# MCU.net
KiCad netlist of a schematic drawn in Altium Designer
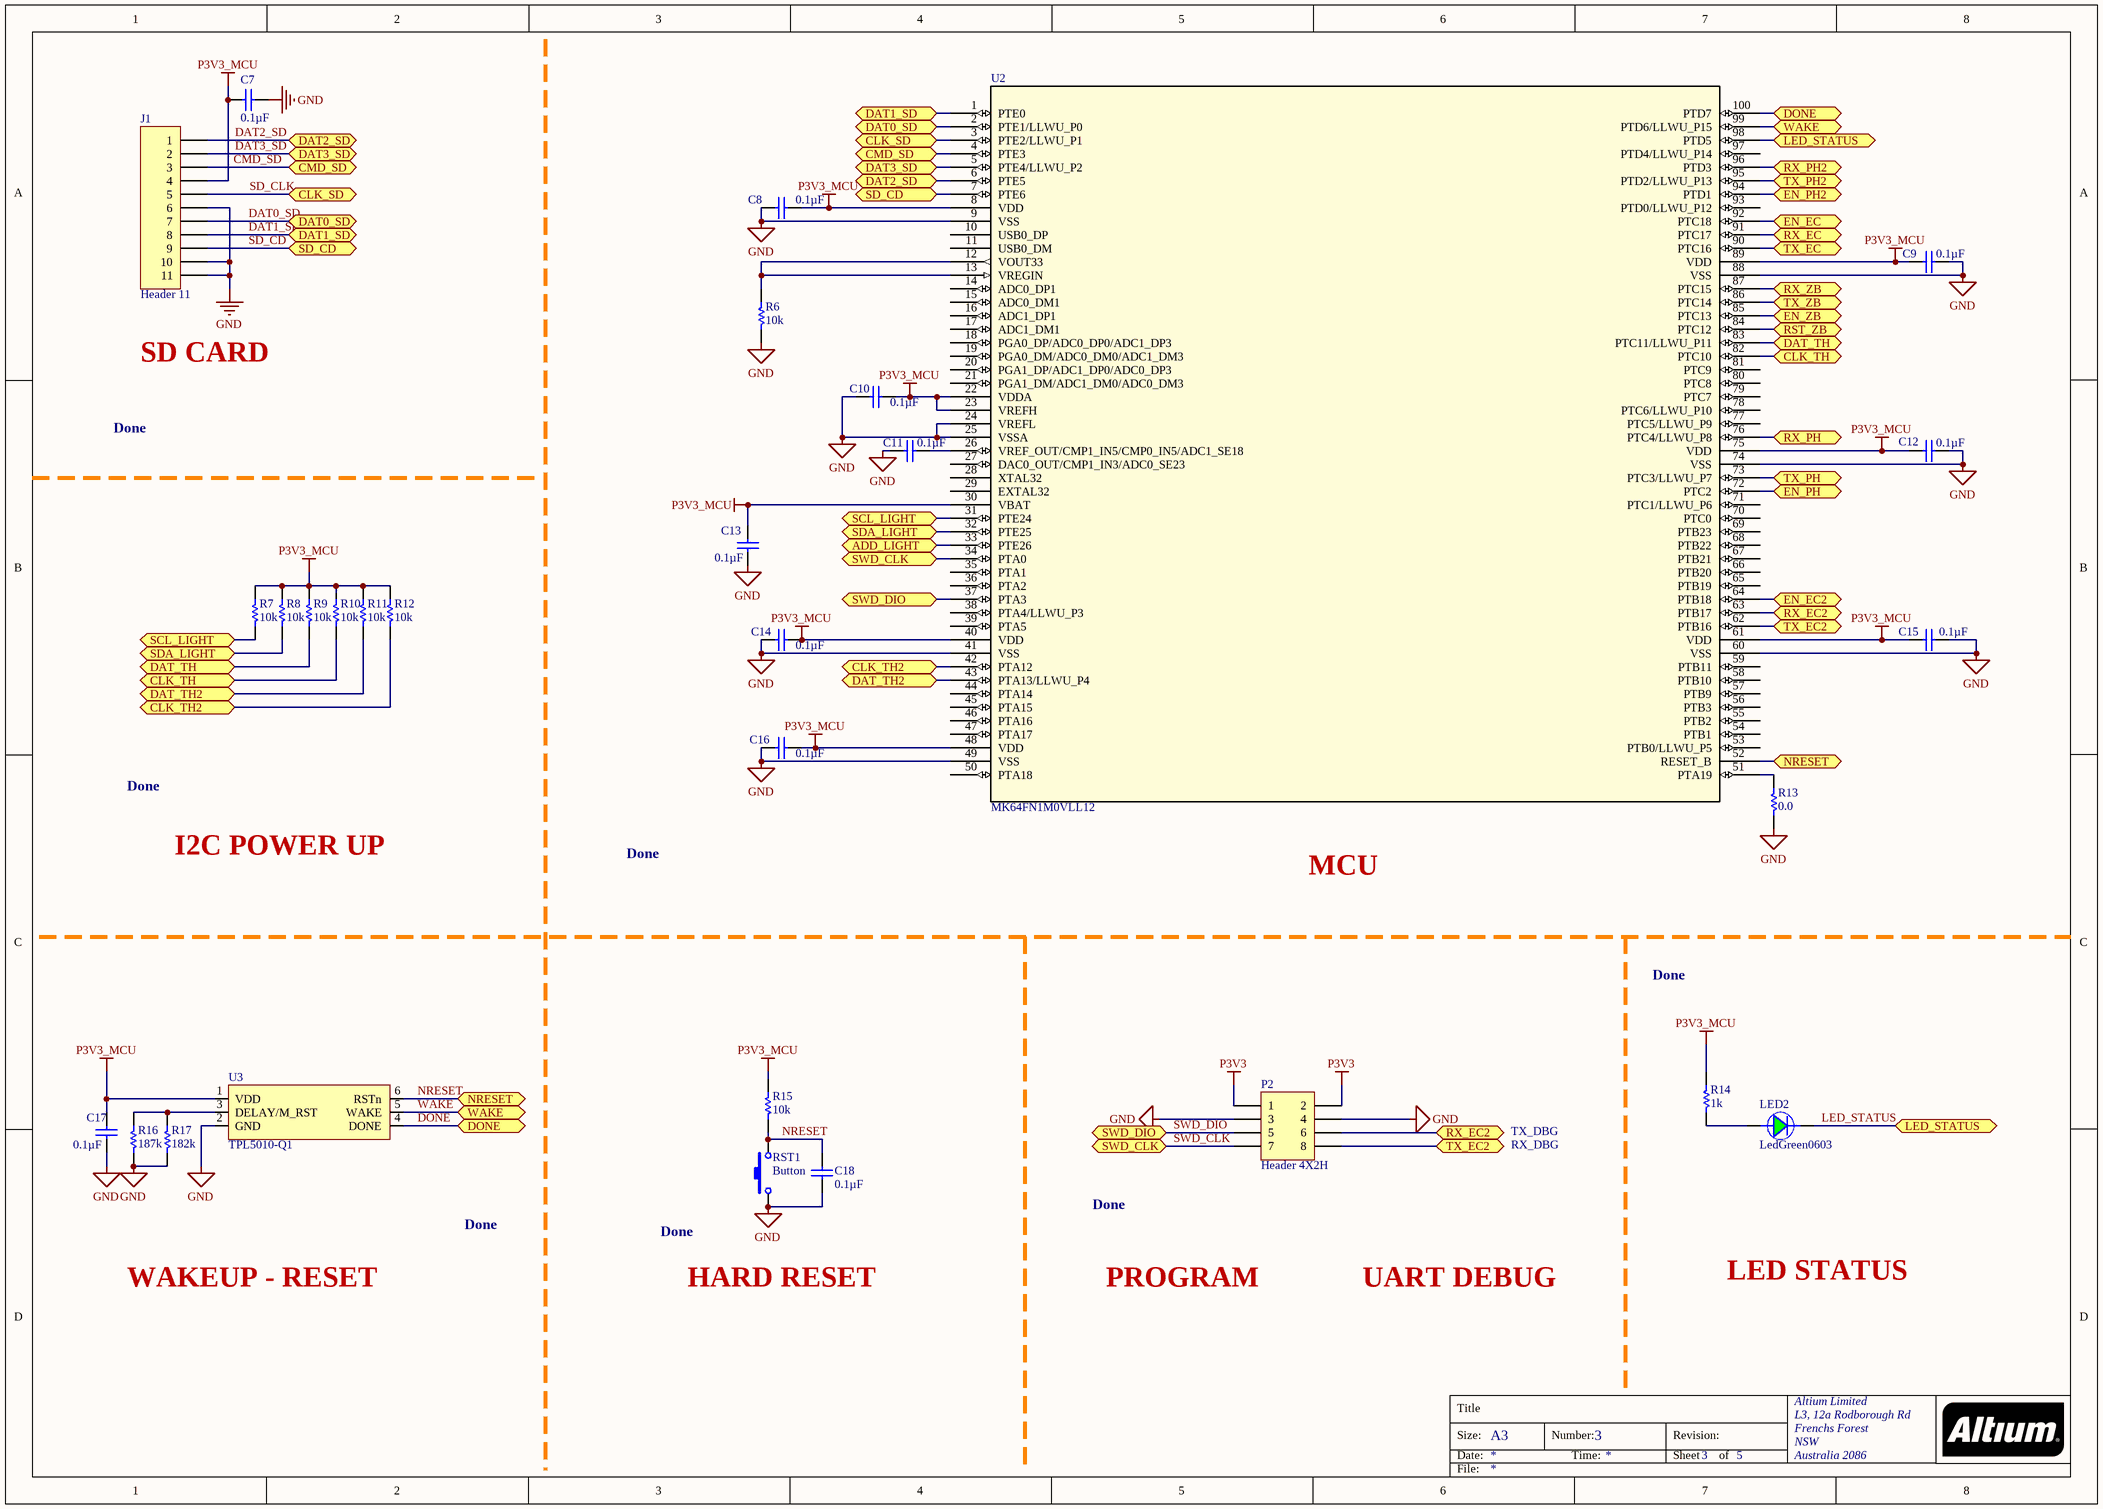
[diagram p0: MCU.SchDoc]

(export (version "E")
  (design (tool "Eeschema 10.0.6"))
  (components
    (comp (ref "C7")
      (value "0.1µF")
      (footprint "C0402M")
      (description "CAP CER 0.1UF 10V X7R 0402")
      (fields
        (field (name "MANUFACTURER") "Taiyo Yuden")
        (field (name "MANUFACTURER PART NUMBER") "LMK105B7104KVHF")
      )
      (libsource (lib "BinhLib") (part "CAP0.1u0402"))
    )
    (comp (ref "C8")
      (value "0.1µF")
      (footprint "C0402M")
      (description "CAP CER 0.1UF 10V X7R 0402")
      (fields
        (field (name "MANUFACTURER") "Taiyo Yuden")
        (field (name "MANUFACTURER PART NUMBER") "LMK105B7104KVHF")
      )
      (libsource (lib "BinhLib") (part "CAP0.1u0402"))
    )
    (comp (ref "C9")
      (value "0.1µF")
      (footprint "C0402M")
      (description "CAP CER 0.1UF 10V X7R 0402")
      (fields
        (field (name "MANUFACTURER") "Taiyo Yuden")
        (field (name "MANUFACTURER PART NUMBER") "LMK105B7104KVHF")
      )
      (libsource (lib "BinhLib") (part "CAP0.1u0402"))
    )
    (comp (ref "C10")
      (value "0.1µF")
      (footprint "C0402M")
      (description "CAP CER 0.1UF 10V X7R 0402")
      (fields
        (field (name "MANUFACTURER") "Taiyo Yuden")
        (field (name "MANUFACTURER PART NUMBER") "LMK105B7104KVHF")
      )
      (libsource (lib "BinhLib") (part "CAP0.1u0402"))
    )
    (comp (ref "C11")
      (value "0.1µF")
      (footprint "C0402M")
      (description "CAP CER 0.1UF 10V X7R 0402")
      (fields
        (field (name "MANUFACTURER") "Taiyo Yuden")
        (field (name "MANUFACTURER PART NUMBER") "LMK105B7104KVHF")
      )
      (libsource (lib "BinhLib") (part "CAP0.1u0402"))
    )
    (comp (ref "C12")
      (value "0.1µF")
      (footprint "C0402M")
      (description "CAP CER 0.1UF 10V X7R 0402")
      (fields
        (field (name "MANUFACTURER") "Taiyo Yuden")
        (field (name "MANUFACTURER PART NUMBER") "LMK105B7104KVHF")
      )
      (libsource (lib "BinhLib") (part "CAP0.1u0402"))
    )
    (comp (ref "C13")
      (value "0.1µF")
      (footprint "C0402M")
      (description "CAP CER 0.1UF 10V X7R 0402")
      (fields
        (field (name "MANUFACTURER") "Taiyo Yuden")
        (field (name "MANUFACTURER PART NUMBER") "LMK105B7104KVHF")
      )
      (libsource (lib "BinhLib") (part "CAP0.1u0402"))
    )
    (comp (ref "C14")
      (value "0.1µF")
      (footprint "C0402M")
      (description "CAP CER 0.1UF 10V X7R 0402")
      (fields
        (field (name "MANUFACTURER") "Taiyo Yuden")
        (field (name "MANUFACTURER PART NUMBER") "LMK105B7104KVHF")
      )
      (libsource (lib "BinhLib") (part "CAP0.1u0402"))
    )
    (comp (ref "C15")
      (value "0.1µF")
      (footprint "C0402M")
      (description "CAP CER 0.1UF 10V X7R 0402")
      (fields
        (field (name "MANUFACTURER") "Taiyo Yuden")
        (field (name "MANUFACTURER PART NUMBER") "LMK105B7104KVHF")
      )
      (libsource (lib "BinhLib") (part "CAP0.1u0402"))
    )
    (comp (ref "C16")
      (value "0.1µF")
      (footprint "C0402M")
      (description "CAP CER 0.1UF 10V X7R 0402")
      (fields
        (field (name "MANUFACTURER") "Taiyo Yuden")
        (field (name "MANUFACTURER PART NUMBER") "LMK105B7104KVHF")
      )
      (libsource (lib "BinhLib") (part "CAP0.1u0402"))
    )
    (comp (ref "C17")
      (value "0.1µF")
      (footprint "C0402M")
      (description "CAP CER 0.1UF 10V X7R 0402")
      (fields
        (field (name "MANUFACTURER") "Taiyo Yuden")
        (field (name "MANUFACTURER PART NUMBER") "LMK105B7104KVHF")
      )
      (libsource (lib "BinhLib") (part "CAP0.1u0402"))
    )
    (comp (ref "C18")
      (value "0.1µF")
      (footprint "C0402M")
      (description "CAP CER 0.1UF 10V X7R 0402")
      (fields
        (field (name "MANUFACTURER") "Taiyo Yuden")
        (field (name "MANUFACTURER PART NUMBER") "LMK105B7104KVHF")
      )
      (libsource (lib "BinhLib") (part "CAP0.1u0402"))
    )
    (comp (ref "J1")
      (value "Header 11")
      (footprint "TF_V3")
      (description "Header, 11-Pin")
      (fields (field (name "PUBLISHER") "Altium Limited"))
      (libsource (lib "Miscellaneous Connectors") (part "Header 11"))
    )
    (comp (ref "LED2")
      (value "LedGreen0603")
      (footprint "0603LED-GREEN")
      (description "LED GREEN CLEAR 0603 SMD")
      (fields
        (field (name "MANUFACTURER") "Everlight Electronics Co Ltd")
        (field (name "MANUFACTURER PART NUMBER") "QTLP601C4TR")
      )
      (libsource (lib "BinhLib") (part "LedGreen0603"))
    )
    (comp (ref "P2")
      (value "Header 4X2H")
      (footprint "HDR2X4")
      (description "Header, 4-Pin, Dual row, Right Angle")
      (fields (field (name "PUBLISHER") "Altium Limited"))
      (libsource (lib "BinhLib") (part "Header 4X2H"))
    )
    (comp (ref "R6")
      (value "10k")
      (footprint "R0603M")
      (description "RES SMD 10K OHM 1% 1/10W 0603")
      (fields
        (field (name "MANUFACTURER") "Panasonic Electronic Components")
        (field (name "MANUFACTURER PART NUMBER") "ERJ-3EKF1002V")
      )
      (libsource (lib "BinhLib") (part "RES10k0603"))
    )
    (comp (ref "R7")
      (value "10k")
      (footprint "R0603M")
      (description "RES SMD 10K OHM 1% 1/10W 0603")
      (fields
        (field (name "MANUFACTURER") "Panasonic Electronic Components")
        (field (name "MANUFACTURER PART NUMBER") "ERJ-3EKF1002V")
      )
      (libsource (lib "BinhLib") (part "RES10k0603"))
    )
    (comp (ref "R8")
      (value "10k")
      (footprint "R0603M")
      (description "RES SMD 10K OHM 1% 1/10W 0603")
      (fields
        (field (name "MANUFACTURER") "Panasonic Electronic Components")
        (field (name "MANUFACTURER PART NUMBER") "ERJ-3EKF1002V")
      )
      (libsource (lib "BinhLib") (part "RES10k0603"))
    )
    (comp (ref "R9")
      (value "10k")
      (footprint "R0603M")
      (description "RES SMD 10K OHM 1% 1/10W 0603")
      (fields
        (field (name "MANUFACTURER") "Panasonic Electronic Components")
        (field (name "MANUFACTURER PART NUMBER") "ERJ-3EKF1002V")
      )
      (libsource (lib "BinhLib") (part "RES10k0603"))
    )
    (comp (ref "R10")
      (value "10k")
      (footprint "R0603M")
      (description "RES SMD 10K OHM 1% 1/10W 0603")
      (fields
        (field (name "MANUFACTURER") "Panasonic Electronic Components")
        (field (name "MANUFACTURER PART NUMBER") "ERJ-3EKF1002V")
      )
      (libsource (lib "BinhLib") (part "RES10k0603"))
    )
    (comp (ref "R11")
      (value "10k")
      (footprint "R0603M")
      (description "RES SMD 10K OHM 1% 1/10W 0603")
      (fields
        (field (name "MANUFACTURER") "Panasonic Electronic Components")
        (field (name "MANUFACTURER PART NUMBER") "ERJ-3EKF1002V")
      )
      (libsource (lib "BinhLib") (part "RES10k0603"))
    )
    (comp (ref "R12")
      (value "10k")
      (footprint "R0603M")
      (description "RES SMD 10K OHM 1% 1/10W 0603")
      (fields
        (field (name "MANUFACTURER") "Panasonic Electronic Components")
        (field (name "MANUFACTURER PART NUMBER") "ERJ-3EKF1002V")
      )
      (libsource (lib "BinhLib") (part "RES10k0603"))
    )
    (comp (ref "R13")
      (value "0.0")
      (footprint "R0603M")
      (description "RES SMD 0.0OHM JUMPER 1/10W 0603")
      (fields
        (field (name "MANUFACTURER") "Panasonic Electronic Components")
        (field (name "MANUFACTURER PART NUMBER") "ERJ-3GEY0R00V")
      )
      (libsource (lib "BinhLib") (part "RES00603"))
    )
    (comp (ref "R14")
      (value "1k")
      (footprint "R0603M")
      (description "RES SMD 1K OHM 1% 1/10W 0603")
      (fields
        (field (name "MANUFACTURER") "Panasonic Electronic Components")
        (field (name "MANUFACTURER PART NUMBER") "ERJ-3EKF1001V")
      )
      (libsource (lib "BinhLib") (part "RES1k0603"))
    )
    (comp (ref "R15")
      (value "10k")
      (footprint "R0603M")
      (description "RES SMD 10K OHM 1% 1/10W 0603")
      (fields
        (field (name "MANUFACTURER") "Panasonic Electronic Components")
        (field (name "MANUFACTURER PART NUMBER") "ERJ-3EKF1002V")
      )
      (libsource (lib "BinhLib") (part "RES10k0603"))
    )
    (comp (ref "R16")
      (value "187k")
      (footprint "R0603M")
      (description "RES SMD 187K OHM 1% 1/10W 0603")
      (fields
        (field (name "MANUFACTURER") "Panasonic Electronic Components")
        (field (name "MANUFACTURER PART NUMBER") "ERJ-3EKF1873V")
      )
      (libsource (lib "BinhLib") (part "Resistor"))
    )
    (comp (ref "R17")
      (value "182k")
      (footprint "R0603M")
      (description "RES SMD 182K OHM 1% 1/10W 0603")
      (fields
        (field (name "MANUFACTURER") "Panasonic Electronic Components")
        (field (name "MANUFACTURER PART NUMBER") "ERJ-3EKF1823V")
      )
      (libsource (lib "BinhLib") (part "Resistor"))
    )
    (comp (ref "RST1") (value "Button") (footprint "SWSMD") (libsource (lib "BinhLib") (part "Button")))
    (comp (ref "U2")
      (value "MK64FN1M0VLL12")
      (footprint "LQFP-100_14X14X1")
      (description "IC MCU 32BIT 1MB FLASH 100LQFP")
      (fields (field (name "MANUFACTURER") "NXP USA Inc."))
      (libsource (lib "BinhLib") (part "MK64FN1M0VLL12"))
    )
    (comp (ref "U3")
      (value "TPL5010-Q1")
      (footprint "SOT23-6")
      (description "IC TIMER W/WATCHDOG 6SOT")
      (fields
        (field (name "MANUFACTURER") "Texas Instruments")
        (field (name "MANUFACTURER PART NUMBER") "TPL5010QDDCRQ1")
      )
      (libsource (lib "BinhLib") (part "TPL5010"))
    )
  )
  (nets
    (net (code "1") (name "/ADD_LIGHT") (class "Default")
      (node (ref "U2") (pin "33") (pinfunction "PTE26_33") (pintype "bidirectional"))
    )
    (net (code "2") (name "/CLK_TH") (class "Default")
      (node (ref "R10") (pin "1") (pinfunction "1_1") (pintype "passive"))
      (node (ref "U2") (pin "82") (pinfunction "PTC10_82") (pintype "bidirectional"))
    )
    (net (code "3") (name "/CLK_TH2") (class "Default")
      (node (ref "R12") (pin "1") (pinfunction "1_1") (pintype "passive"))
      (node (ref "U2") (pin "42") (pinfunction "PTA12_42") (pintype "bidirectional"))
    )
    (net (code "4") (name "/CMD_SD") (class "Default")
      (node (ref "J1") (pin "3") (pinfunction "3_3") (pintype "passive"))
      (node (ref "U2") (pin "4") (pinfunction "PTE3_4") (pintype "bidirectional"))
    )
    (net (code "5") (name "/DAT0_SD") (class "Default")
      (node (ref "J1") (pin "7") (pinfunction "7_7") (pintype "passive"))
      (node (ref "U2") (pin "2") (pinfunction "PTE1/LLWU_P0_2") (pintype "bidirectional"))
    )
    (net (code "6") (name "/DAT1_SD") (class "Default")
      (node (ref "J1") (pin "8") (pinfunction "8_8") (pintype "passive"))
      (node (ref "U2") (pin "1") (pinfunction "PTE0_1") (pintype "bidirectional"))
    )
    (net (code "7") (name "/DAT2_SD") (class "Default")
      (node (ref "J1") (pin "1") (pinfunction "1_1") (pintype "passive"))
      (node (ref "U2") (pin "6") (pinfunction "PTE5_6") (pintype "bidirectional"))
    )
    (net (code "8") (name "/DAT3_SD") (class "Default")
      (node (ref "J1") (pin "2") (pinfunction "2_2") (pintype "passive"))
      (node (ref "U2") (pin "5") (pinfunction "PTE4/LLWU_P2_5") (pintype "bidirectional"))
    )
    (net (code "9") (name "/DAT_TH") (class "Default")
      (node (ref "R9") (pin "1") (pinfunction "1_1") (pintype "passive"))
      (node (ref "U2") (pin "83") (pinfunction "PTC11/LLWU_P11_83") (pintype "bidirectional"))
    )
    (net (code "10") (name "/DAT_TH2") (class "Default")
      (node (ref "R11") (pin "1") (pinfunction "1_1") (pintype "passive"))
      (node (ref "U2") (pin "43") (pinfunction "PTA13/LLWU_P4_43") (pintype "bidirectional"))
    )
    (net (code "11") (name "/DONE") (class "Default")
      (node (ref "U2") (pin "100") (pinfunction "PTD7_100") (pintype "bidirectional"))
      (node (ref "U3") (pin "4") (pinfunction "DONE_4") (pintype "passive"))
    )
    (net (code "12") (name "/EN_EC") (class "Default")
      (node (ref "U2") (pin "92") (pinfunction "PTC18_92") (pintype "bidirectional"))
    )
    (net (code "13") (name "/EN_EC2") (class "Default")
      (node (ref "U2") (pin "64") (pinfunction "PTB18_64") (pintype "bidirectional"))
    )
    (net (code "14") (name "/EN_PH") (class "Default")
      (node (ref "U2") (pin "72") (pinfunction "PTC2_72") (pintype "bidirectional"))
    )
    (net (code "15") (name "/EN_PH2") (class "Default")
      (node (ref "U2") (pin "94") (pinfunction "PTD1_94") (pintype "bidirectional"))
    )
    (net (code "16") (name "/EN_ZB") (class "Default")
      (node (ref "U2") (pin "85") (pinfunction "PTC13_85") (pintype "bidirectional"))
    )
    (net (code "17") (name "/LED_STATUS") (class "Default")
      (node (ref "LED2") (pin "2") (pinfunction "Katot_2") (pintype "passive"))
      (node (ref "U2") (pin "98") (pinfunction "PTD5_98") (pintype "bidirectional"))
    )
    (net (code "18") (name "/NRESET") (class "Default")
      (node (ref "C18") (pin "2") (pintype "passive"))
      (node (ref "R15") (pin "2") (pinfunction "2_2") (pintype "passive"))
      (node (ref "RST1") (pin "2") (pinfunction "2_2") (pintype "passive"))
      (node (ref "U2") (pin "52") (pinfunction "RESET_B_52") (pintype "passive"))
      (node (ref "U3") (pin "6") (pinfunction "RSTn_6") (pintype "passive"))
    )
    (net (code "19") (name "/RST_ZB") (class "Default")
      (node (ref "U2") (pin "84") (pinfunction "PTC12_84") (pintype "bidirectional"))
    )
    (net (code "20") (name "/RX_EC") (class "Default")
      (node (ref "U2") (pin "91") (pinfunction "PTC17_91") (pintype "bidirectional"))
    )
    (net (code "21") (name "/RX_EC2") (class "Default")
      (node (ref "P2") (pin "6") (pinfunction "6_6") (pintype "passive"))
      (node (ref "U2") (pin "63") (pinfunction "PTB17_63") (pintype "bidirectional"))
    )
    (net (code "22") (name "/RX_PH") (class "Default")
      (node (ref "U2") (pin "76") (pinfunction "PTC4/LLWU_P8_76") (pintype "bidirectional"))
    )
    (net (code "23") (name "/RX_PH2") (class "Default")
      (node (ref "U2") (pin "96") (pinfunction "PTD3_96") (pintype "bidirectional"))
    )
    (net (code "24") (name "/RX_ZB") (class "Default")
      (node (ref "U2") (pin "87") (pinfunction "PTC15_87") (pintype "bidirectional"))
    )
    (net (code "25") (name "/SCL_LIGHT") (class "Default")
      (node (ref "R7") (pin "1") (pinfunction "1_1") (pintype "passive"))
      (node (ref "U2") (pin "31") (pinfunction "PTE24_31") (pintype "bidirectional"))
    )
    (net (code "26") (name "/SDA_LIGHT") (class "Default")
      (node (ref "R8") (pin "1") (pinfunction "1_1") (pintype "passive"))
      (node (ref "U2") (pin "32") (pinfunction "PTE25_32") (pintype "bidirectional"))
    )
    (net (code "27") (name "/SD_CD") (class "Default")
      (node (ref "J1") (pin "9") (pinfunction "9_9") (pintype "passive"))
      (node (ref "U2") (pin "7") (pinfunction "PTE6_7") (pintype "bidirectional"))
    )
    (net (code "28") (name "/SD_CLK") (class "Default")
      (node (ref "J1") (pin "5") (pinfunction "5_5") (pintype "passive"))
      (node (ref "U2") (pin "3") (pinfunction "PTE2/LLWU_P1_3") (pintype "bidirectional"))
    )
    (net (code "29") (name "/SWD_CLK") (class "Default")
      (node (ref "P2") (pin "7") (pinfunction "7_7") (pintype "passive"))
      (node (ref "U2") (pin "34") (pinfunction "PTA0_34") (pintype "bidirectional"))
    )
    (net (code "30") (name "/SWD_DIO") (class "Default")
      (node (ref "P2") (pin "5") (pinfunction "5_5") (pintype "passive"))
      (node (ref "U2") (pin "37") (pinfunction "PTA3_37") (pintype "bidirectional"))
    )
    (net (code "31") (name "/TX_EC") (class "Default")
      (node (ref "U2") (pin "90") (pinfunction "PTC16_90") (pintype "bidirectional"))
    )
    (net (code "32") (name "/TX_EC2") (class "Default")
      (node (ref "P2") (pin "8") (pinfunction "8_8") (pintype "passive"))
      (node (ref "U2") (pin "62") (pinfunction "PTB16_62") (pintype "bidirectional"))
    )
    (net (code "33") (name "/TX_PH") (class "Default")
      (node (ref "U2") (pin "73") (pinfunction "PTC3/LLWU_P7_73") (pintype "bidirectional"))
    )
    (net (code "34") (name "/TX_PH2") (class "Default")
      (node (ref "U2") (pin "95") (pinfunction "PTD2/LLWU_P13_95") (pintype "bidirectional"))
    )
    (net (code "35") (name "/TX_ZB") (class "Default")
      (node (ref "U2") (pin "86") (pinfunction "PTC14_86") (pintype "bidirectional"))
    )
    (net (code "36") (name "/WAKE") (class "Default")
      (node (ref "U2") (pin "99") (pinfunction "PTD6/LLWU_P15_99") (pintype "bidirectional"))
      (node (ref "U3") (pin "5") (pinfunction "WAKE_5") (pintype "passive"))
    )
    (net (code "37") (name "GND") (class "Default")
      (node (ref "C10") (pin "2") (pintype "passive"))
      (node (ref "C11") (pin "2") (pintype "passive"))
      (node (ref "C12") (pin "2") (pintype "passive"))
      (node (ref "C13") (pin "2") (pintype "passive"))
      (node (ref "C14") (pin "1") (pintype "passive"))
      (node (ref "C15") (pin "2") (pintype "passive"))
      (node (ref "C16") (pin "1") (pintype "passive"))
      (node (ref "C17") (pin "1") (pintype "passive"))
      (node (ref "C18") (pin "1") (pintype "passive"))
      (node (ref "C7") (pin "2") (pintype "passive"))
      (node (ref "C8") (pin "2") (pintype "passive"))
      (node (ref "C9") (pin "2") (pintype "passive"))
      (node (ref "J1") (pin "10") (pinfunction "10_10") (pintype "passive"))
      (node (ref "J1") (pin "11") (pinfunction "11_11") (pintype "passive"))
      (node (ref "J1") (pin "6") (pinfunction "6_6") (pintype "passive"))
      (node (ref "P2") (pin "3") (pinfunction "3_3") (pintype "passive"))
      (node (ref "P2") (pin "4") (pinfunction "4_4") (pintype "passive"))
      (node (ref "R13") (pin "1") (pinfunction "1_1") (pintype "passive"))
      (node (ref "R16") (pin "1") (pinfunction "1_1") (pintype "passive"))
      (node (ref "R17") (pin "1") (pinfunction "1_1") (pintype "passive"))
      (node (ref "R6") (pin "1") (pinfunction "1_1") (pintype "passive"))
      (node (ref "RST1") (pin "1") (pinfunction "1_1") (pintype "passive"))
      (node (ref "U2") (pin "24") (pinfunction "VREFL_24") (pintype "power_in"))
      (node (ref "U2") (pin "25") (pinfunction "VSSA_25") (pintype "power_in"))
      (node (ref "U2") (pin "41") (pinfunction "VSS_41") (pintype "power_in"))
      (node (ref "U2") (pin "49") (pinfunction "VSS_49") (pintype "power_in"))
      (node (ref "U2") (pin "60") (pinfunction "VSS_60") (pintype "power_in"))
      (node (ref "U2") (pin "74") (pinfunction "VSS_74") (pintype "power_in"))
      (node (ref "U2") (pin "88") (pinfunction "VSS_88") (pintype "power_in"))
      (node (ref "U2") (pin "9") (pinfunction "VSS_9") (pintype "power_in"))
      (node (ref "U3") (pin "2") (pinfunction "GND_2") (pintype "passive"))
    )
    (net (code "38") (name "Net-(LED2-anot)") (class "Default")
      (node (ref "LED2") (pin "1") (pinfunction "anot_1") (pintype "passive"))
      (node (ref "R14") (pin "2") (pinfunction "2_2") (pintype "passive"))
    )
    (net (code "39") (name "Net-(U2-PTA19)") (class "Default")
      (node (ref "R13") (pin "2") (pinfunction "2_2") (pintype "passive"))
      (node (ref "U2") (pin "51") (pinfunction "PTA19_51") (pintype "bidirectional"))
    )
    (net (code "40") (name "Net-(U2-VOUT33)") (class "Default")
      (node (ref "R6") (pin "2") (pinfunction "2_2") (pintype "passive"))
      (node (ref "U2") (pin "12") (pinfunction "VOUT33_12") (pintype "output"))
      (node (ref "U2") (pin "13") (pinfunction "VREGIN_13") (pintype "input"))
    )
    (net (code "41") (name "Net-(U2-VREF_OUT{slash}CMP1_IN5{slash}CMP0_IN5{slash}ADC1_SE18)") (class "Default")
      (node (ref "C11") (pin "1") (pintype "passive"))
      (node (ref "U2") (pin "26") (pinfunction "VREF_OUT/CMP1_IN5/CMP0_IN5/ADC1_SE18_26") (pintype "bidirectional"))
    )
    (net (code "42") (name "Net-(U3-DELAY{slash}M_RST)") (class "Default")
      (node (ref "R16") (pin "2") (pinfunction "2_2") (pintype "passive"))
      (node (ref "R17") (pin "2") (pinfunction "2_2") (pintype "passive"))
      (node (ref "U3") (pin "3") (pinfunction "DELAY/M_RST_3") (pintype "passive"))
    )
    (net (code "43") (name "P3V3") (class "Default")
      (node (ref "P2") (pin "1") (pinfunction "1_1") (pintype "passive"))
      (node (ref "P2") (pin "2") (pinfunction "2_2") (pintype "passive"))
    )
    (net (code "44") (name "P3V3_MCU") (class "Default")
      (node (ref "C10") (pin "1") (pintype "passive"))
      (node (ref "C12") (pin "1") (pintype "passive"))
      (node (ref "C13") (pin "1") (pintype "passive"))
      (node (ref "C14") (pin "2") (pintype "passive"))
      (node (ref "C15") (pin "1") (pintype "passive"))
      (node (ref "C16") (pin "2") (pintype "passive"))
      (node (ref "C17") (pin "2") (pintype "passive"))
      (node (ref "C7") (pin "1") (pintype "passive"))
      (node (ref "C8") (pin "1") (pintype "passive"))
      (node (ref "C9") (pin "1") (pintype "passive"))
      (node (ref "J1") (pin "4") (pinfunction "4_4") (pintype "passive"))
      (node (ref "R10") (pin "2") (pinfunction "2_2") (pintype "passive"))
      (node (ref "R11") (pin "2") (pinfunction "2_2") (pintype "passive"))
      (node (ref "R12") (pin "2") (pinfunction "2_2") (pintype "passive"))
      (node (ref "R14") (pin "1") (pinfunction "1_1") (pintype "passive"))
      (node (ref "R15") (pin "1") (pinfunction "1_1") (pintype "passive"))
      (node (ref "R7") (pin "2") (pinfunction "2_2") (pintype "passive"))
      (node (ref "R8") (pin "2") (pinfunction "2_2") (pintype "passive"))
      (node (ref "R9") (pin "2") (pinfunction "2_2") (pintype "passive"))
      (node (ref "U2") (pin "22") (pinfunction "VDDA_22") (pintype "power_in"))
      (node (ref "U2") (pin "23") (pinfunction "VREFH_23") (pintype "power_in"))
      (node (ref "U2") (pin "30") (pinfunction "VBAT_30") (pintype "power_in"))
      (node (ref "U2") (pin "40") (pinfunction "VDD_40") (pintype "power_in"))
      (node (ref "U2") (pin "48") (pinfunction "VDD_48") (pintype "power_in"))
      (node (ref "U2") (pin "61") (pinfunction "VDD_61") (pintype "power_in"))
      (node (ref "U2") (pin "75") (pinfunction "VDD_75") (pintype "power_in"))
      (node (ref "U2") (pin "8") (pinfunction "VDD_8") (pintype "power_in"))
      (node (ref "U2") (pin "89") (pinfunction "VDD_89") (pintype "power_in"))
      (node (ref "U3") (pin "1") (pinfunction "VDD_1") (pintype "passive"))
    )
    (net (code "45") (name "unconnected-(U2-ADC0_DM1-Pad15)") (class "Default")
      (node (ref "U2") (pin "15") (pinfunction "ADC0_DM1_15") (pintype "bidirectional"))
    )
    (net (code "46") (name "unconnected-(U2-ADC0_DP1-Pad14)") (class "Default")
      (node (ref "U2") (pin "14") (pinfunction "ADC0_DP1_14") (pintype "bidirectional"))
    )
    (net (code "47") (name "unconnected-(U2-ADC1_DM1-Pad17)") (class "Default")
      (node (ref "U2") (pin "17") (pinfunction "ADC1_DM1_17") (pintype "bidirectional"))
    )
    (net (code "48") (name "unconnected-(U2-ADC1_DP1-Pad16)") (class "Default")
      (node (ref "U2") (pin "16") (pinfunction "ADC1_DP1_16") (pintype "bidirectional"))
    )
    (net (code "49") (name "unconnected-(U2-DAC0_OUT{slash}CMP1_IN3{slash}ADC0_SE23-Pad27)") (class "Default")
      (node (ref "U2") (pin "27") (pinfunction "DAC0_OUT/CMP1_IN3/ADC0_SE23_27") (pintype "bidirectional"))
    )
    (net (code "50") (name "unconnected-(U2-EXTAL32-Pad29)") (class "Default")
      (node (ref "U2") (pin "29") (pinfunction "EXTAL32_29") (pintype "passive"))
    )
    (net (code "51") (name "unconnected-(U2-PGA0_DM{slash}ADC0_DM0{slash}ADC1_DM3-Pad19)") (class "Default")
      (node (ref "U2") (pin "19") (pinfunction "PGA0_DM/ADC0_DM0/ADC1_DM3_19") (pintype "bidirectional"))
    )
    (net (code "52") (name "unconnected-(U2-PGA0_DP{slash}ADC0_DP0{slash}ADC1_DP3-Pad18)") (class "Default")
      (node (ref "U2") (pin "18") (pinfunction "PGA0_DP/ADC0_DP0/ADC1_DP3_18") (pintype "bidirectional"))
    )
    (net (code "53") (name "unconnected-(U2-PGA1_DM{slash}ADC1_DM0{slash}ADC0_DM3-Pad21)") (class "Default")
      (node (ref "U2") (pin "21") (pinfunction "PGA1_DM/ADC1_DM0/ADC0_DM3_21") (pintype "bidirectional"))
    )
    (net (code "54") (name "unconnected-(U2-PGA1_DP{slash}ADC1_DP0{slash}ADC0_DP3-Pad20)") (class "Default")
      (node (ref "U2") (pin "20") (pinfunction "PGA1_DP/ADC1_DP0/ADC0_DP3_20") (pintype "bidirectional"))
    )
    (net (code "55") (name "unconnected-(U2-PTA1-Pad35)") (class "Default")
      (node (ref "U2") (pin "35") (pinfunction "PTA1_35") (pintype "bidirectional"))
    )
    (net (code "56") (name "unconnected-(U2-PTA2-Pad36)") (class "Default")
      (node (ref "U2") (pin "36") (pinfunction "PTA2_36") (pintype "bidirectional"))
    )
    (net (code "57") (name "unconnected-(U2-PTA4{slash}LLWU_P3-Pad38)") (class "Default")
      (node (ref "U2") (pin "38") (pinfunction "PTA4/LLWU_P3_38") (pintype "bidirectional"))
    )
    (net (code "58") (name "unconnected-(U2-PTA5-Pad39)") (class "Default")
      (node (ref "U2") (pin "39") (pinfunction "PTA5_39") (pintype "bidirectional"))
    )
    (net (code "59") (name "unconnected-(U2-PTA14-Pad44)") (class "Default")
      (node (ref "U2") (pin "44") (pinfunction "PTA14_44") (pintype "bidirectional"))
    )
    (net (code "60") (name "unconnected-(U2-PTA15-Pad45)") (class "Default")
      (node (ref "U2") (pin "45") (pinfunction "PTA15_45") (pintype "bidirectional"))
    )
    (net (code "61") (name "unconnected-(U2-PTA16-Pad46)") (class "Default")
      (node (ref "U2") (pin "46") (pinfunction "PTA16_46") (pintype "bidirectional"))
    )
    (net (code "62") (name "unconnected-(U2-PTA17-Pad47)") (class "Default")
      (node (ref "U2") (pin "47") (pinfunction "PTA17_47") (pintype "bidirectional"))
    )
    (net (code "63") (name "unconnected-(U2-PTA18-Pad50)") (class "Default")
      (node (ref "U2") (pin "50") (pinfunction "PTA18_50") (pintype "bidirectional"))
    )
    (net (code "64") (name "unconnected-(U2-PTB0{slash}LLWU_P5-Pad53)") (class "Default")
      (node (ref "U2") (pin "53") (pinfunction "PTB0/LLWU_P5_53") (pintype "bidirectional"))
    )
    (net (code "65") (name "unconnected-(U2-PTB1-Pad54)") (class "Default")
      (node (ref "U2") (pin "54") (pinfunction "PTB1_54") (pintype "bidirectional"))
    )
    (net (code "66") (name "unconnected-(U2-PTB2-Pad55)") (class "Default")
      (node (ref "U2") (pin "55") (pinfunction "PTB2_55") (pintype "bidirectional"))
    )
    (net (code "67") (name "unconnected-(U2-PTB3-Pad56)") (class "Default")
      (node (ref "U2") (pin "56") (pinfunction "PTB3_56") (pintype "bidirectional"))
    )
    (net (code "68") (name "unconnected-(U2-PTB9-Pad57)") (class "Default")
      (node (ref "U2") (pin "57") (pinfunction "PTB9_57") (pintype "bidirectional"))
    )
    (net (code "69") (name "unconnected-(U2-PTB10-Pad58)") (class "Default")
      (node (ref "U2") (pin "58") (pinfunction "PTB10_58") (pintype "bidirectional"))
    )
    (net (code "70") (name "unconnected-(U2-PTB11-Pad59)") (class "Default")
      (node (ref "U2") (pin "59") (pinfunction "PTB11_59") (pintype "bidirectional"))
    )
    (net (code "71") (name "unconnected-(U2-PTB19-Pad65)") (class "Default")
      (node (ref "U2") (pin "65") (pinfunction "PTB19_65") (pintype "bidirectional"))
    )
    (net (code "72") (name "unconnected-(U2-PTB20-Pad66)") (class "Default")
      (node (ref "U2") (pin "66") (pinfunction "PTB20_66") (pintype "bidirectional"))
    )
    (net (code "73") (name "unconnected-(U2-PTB21-Pad67)") (class "Default")
      (node (ref "U2") (pin "67") (pinfunction "PTB21_67") (pintype "bidirectional"))
    )
    (net (code "74") (name "unconnected-(U2-PTB22-Pad68)") (class "Default")
      (node (ref "U2") (pin "68") (pinfunction "PTB22_68") (pintype "bidirectional"))
    )
    (net (code "75") (name "unconnected-(U2-PTB23-Pad69)") (class "Default")
      (node (ref "U2") (pin "69") (pinfunction "PTB23_69") (pintype "bidirectional"))
    )
    (net (code "76") (name "unconnected-(U2-PTC0-Pad70)") (class "Default")
      (node (ref "U2") (pin "70") (pinfunction "PTC0_70") (pintype "bidirectional"))
    )
    (net (code "77") (name "unconnected-(U2-PTC1{slash}LLWU_P6-Pad71)") (class "Default")
      (node (ref "U2") (pin "71") (pinfunction "PTC1/LLWU_P6_71") (pintype "bidirectional"))
    )
    (net (code "78") (name "unconnected-(U2-PTC5{slash}LLWU_P9-Pad77)") (class "Default")
      (node (ref "U2") (pin "77") (pinfunction "PTC5/LLWU_P9_77") (pintype "bidirectional"))
    )
    (net (code "79") (name "unconnected-(U2-PTC6{slash}LLWU_P10-Pad78)") (class "Default")
      (node (ref "U2") (pin "78") (pinfunction "PTC6/LLWU_P10_78") (pintype "bidirectional"))
    )
    (net (code "80") (name "unconnected-(U2-PTC7-Pad79)") (class "Default")
      (node (ref "U2") (pin "79") (pinfunction "PTC7_79") (pintype "bidirectional"))
    )
    (net (code "81") (name "unconnected-(U2-PTC8-Pad80)") (class "Default")
      (node (ref "U2") (pin "80") (pinfunction "PTC8_80") (pintype "bidirectional"))
    )
    (net (code "82") (name "unconnected-(U2-PTC9-Pad81)") (class "Default")
      (node (ref "U2") (pin "81") (pinfunction "PTC9_81") (pintype "bidirectional"))
    )
    (net (code "83") (name "unconnected-(U2-PTD0{slash}LLWU_P12-Pad93)") (class "Default")
      (node (ref "U2") (pin "93") (pinfunction "PTD0/LLWU_P12_93") (pintype "bidirectional"))
    )
    (net (code "84") (name "unconnected-(U2-PTD4{slash}LLWU_P14-Pad97)") (class "Default")
      (node (ref "U2") (pin "97") (pinfunction "PTD4/LLWU_P14_97") (pintype "bidirectional"))
    )
    (net (code "85") (name "unconnected-(U2-USB0_DM-Pad11)") (class "Default")
      (node (ref "U2") (pin "11") (pinfunction "USB0_DM_11") (pintype "passive"))
    )
    (net (code "86") (name "unconnected-(U2-USB0_DP-Pad10)") (class "Default")
      (node (ref "U2") (pin "10") (pinfunction "USB0_DP_10") (pintype "passive"))
    )
    (net (code "87") (name "unconnected-(U2-XTAL32-Pad28)") (class "Default")
      (node (ref "U2") (pin "28") (pinfunction "XTAL32_28") (pintype "passive"))
    )
  )
)
